# Power_CH340T.net
KiCad netlist of a schematic drawn in Altium Designer
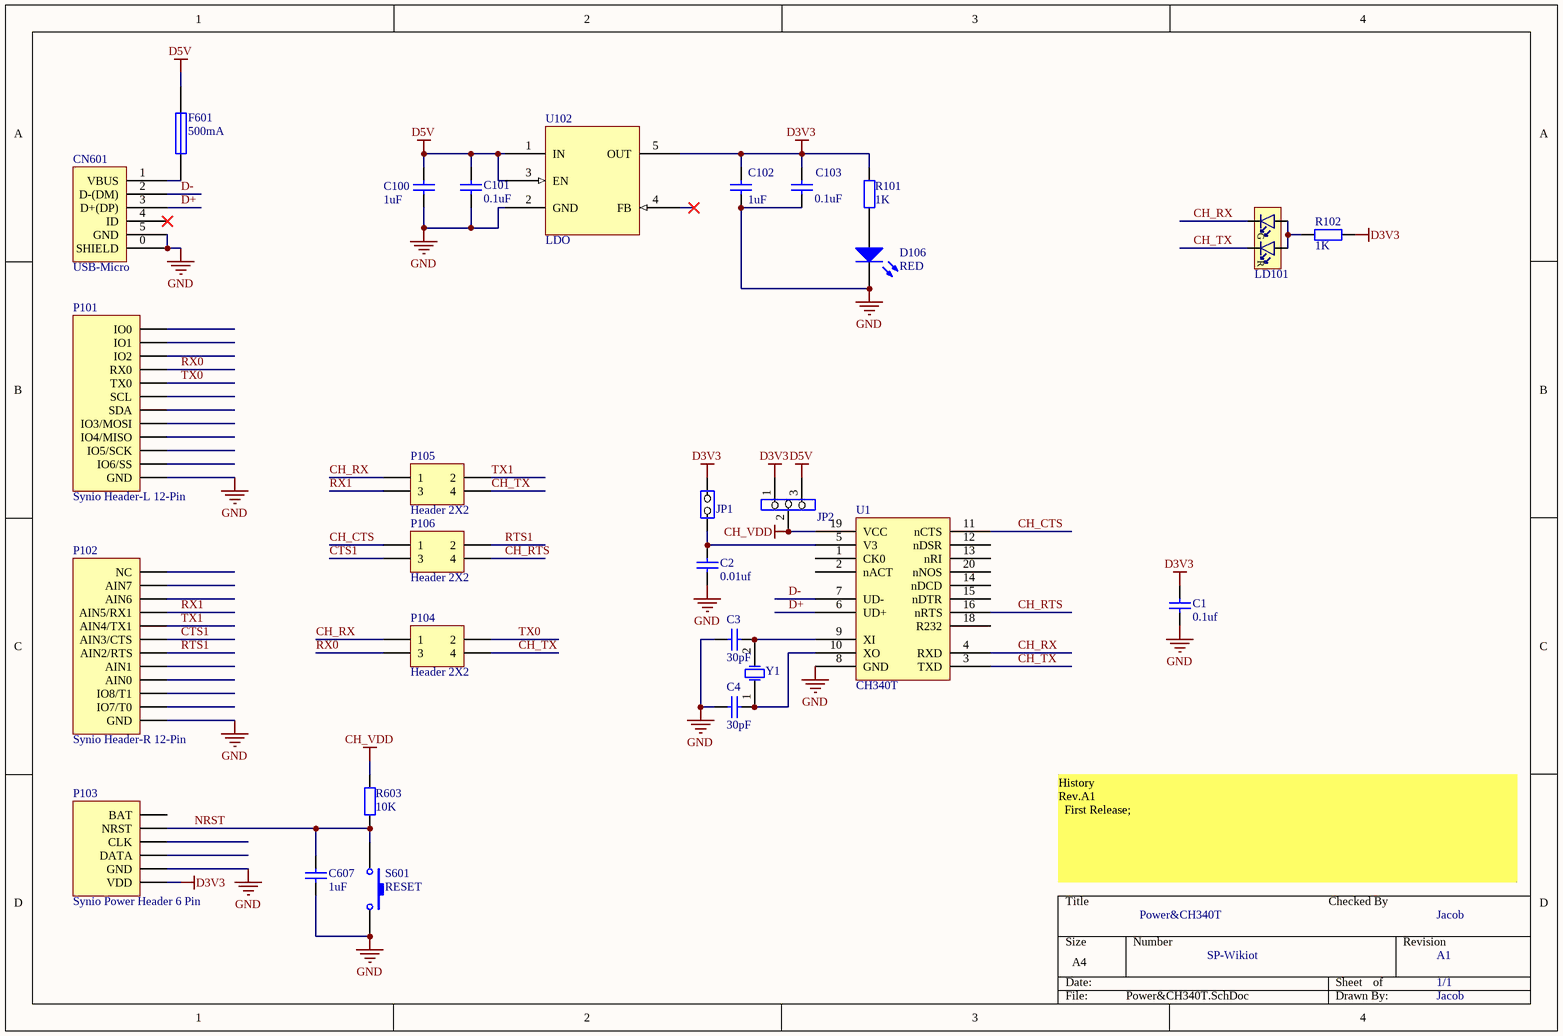
[diagram p0: Power&CH340T.SchDoc]

(export (version "E")
  (design (tool "Eeschema 10.0.6"))
  (components
    (comp (ref "C1")
      (value "0.1uf")
      (footprint "C0603L")
      (description "Capacitor")
      (fields (field (name "Comment") "Cap") (field (name "PUBLISHER") "Altium Limited"))
      (libsource (lib "myintlib") (part "Cap"))
    )
    (comp (ref "C2")
      (value "0.01uf")
      (footprint "C0603L")
      (description "Capacitor")
      (fields (field (name "Comment") "Cap") (field (name "PUBLISHER") "Altium Limited"))
      (libsource (lib "myintlib") (part "Cap"))
    )
    (comp (ref "C3")
      (value "30pF")
      (footprint "C0603L")
      (description "Capacitor")
      (fields (field (name "Comment") "Cap") (field (name "PUBLISHER") "Altium Limited"))
      (libsource (lib "Miscellaneous Devices") (part "Cap"))
    )
    (comp (ref "C4")
      (value "30pF")
      (footprint "C0603L")
      (description "Capacitor")
      (fields (field (name "Comment") "Cap") (field (name "PUBLISHER") "Altium Limited"))
      (libsource (lib "Miscellaneous Devices") (part "Cap"))
    )
    (comp (ref "C100")
      (value "1uF")
      (footprint "0603M")
      (description "Capacitor")
      (libsource (lib "Studio") (part "Cap"))
    )
    (comp (ref "C101")
      (value "0.1uF")
      (footprint "0603M")
      (description "Capacitor")
      (libsource (lib "Studio") (part "Cap"))
    )
    (comp (ref "C102")
      (value "1uF")
      (footprint "0603M")
      (description "Capacitor")
      (libsource (lib "Studio") (part "Cap"))
    )
    (comp (ref "C103")
      (value "0.1uF")
      (footprint "0603M")
      (description "Capacitor")
      (libsource (lib "Studio") (part "Cap"))
    )
    (comp (ref "C607")
      (value "1uF")
      (footprint "C0603L")
      (description "Capacitor")
      (fields (field (name "PUBLISHER") "Altium Limited"))
      (libsource (lib "Miscellaneous Devices") (part "Cap"))
    )
    (comp (ref "CN601")
      (value "USB-Micro")
      (footprint "USB-MICRO-Female-Lite")
      (libsource (lib "Connector") (part "USB-Micro"))
    )
    (comp (ref "D106")
      (value "RED")
      (footprint "0603pn")
      (description "Typical INFRARED GaAs LED")
      (fields (field (name "PUBLISHER") "Altium Limited"))
      (libsource (lib "Miscellaneous Devices") (part "LED0"))
    )
    (comp (ref "F601")
      (value "500mA")
      (footprint "0805")
      (description "Fuse")
      (fields (field (name "PUBLISHER") "Altium Limited"))
      (libsource (lib "Studio") (part "Fuse 1"))
    )
    (comp (ref "JP1")
      (value "Jumper2-2")
      (footprint "SIP2")
      (description "Jumper2")
      (libsource (lib "Misc") (part "Jumper2-2"))
    )
    (comp (ref "JP2") (value "Jumper3") (footprint "SIP3") (libsource (lib "Misc") (part "Jumper3")))
    (comp (ref "LD101")
      (value "LTST-C195KGJRKT")
      (footprint "0805-LED-Bi")
      (description "Avago, HSMF-A203 Bi-Color LED")
      (fields
        (field (name "MANUFACTURER") "Lite-On Inc")
        (field (name "2ND SOURCE PART NUMBER") "859-LTST-C195KGJRKT")
        (field (name "PUBLISHER") "Nordic Semiconductor")
      )
      (libsource (lib "Misc") (part "LED-DUAL"))
    )
    (comp (ref "P101")
      (value "Synio Header-L 12-Pin")
      (footprint "HDR1X12")
      (description "Synio Header-L, 12-Pin")
      (fields (field (name "PUBLISHER") "Altium Limited"))
      (libsource (lib "Connector") (part "Synio Header-L 12-Pin"))
    )
    (comp (ref "P102")
      (value "Synio Header-R 12-Pin")
      (footprint "HDR1X12")
      (description "Synio Header-R, 12-Pin")
      (fields (field (name "PUBLISHER") "Altium Limited"))
      (libsource (lib "Connector") (part "Synio Header-R 12-Pin"))
    )
    (comp (ref "P103")
      (value "Synio Power Header 6 Pin")
      (footprint "HDR1X6/2.54MM")
      (libsource (lib "Connector") (part "Synio Power Header 6 Pin"))
    )
    (comp (ref "P104")
      (value "Header 2X2")
      (footprint "HDR2X2/2.54MM")
      (description "Header, 2-Pin, Dual row")
      (fields (field (name "PUBLISHER") "Altium Limited"))
      (libsource (lib "Miscellaneous Connectors") (part "Header 2X2"))
    )
    (comp (ref "P105")
      (value "Header 2X2")
      (footprint "HDR2X2/2.54MM")
      (description "Header, 2-Pin, Dual row")
      (fields (field (name "PUBLISHER") "Altium Limited"))
      (libsource (lib "Miscellaneous Connectors") (part "Header 2X2"))
    )
    (comp (ref "P106")
      (value "Header 2X2")
      (footprint "HDR2X2/2.54MM")
      (description "Header, 2-Pin, Dual row")
      (fields (field (name "PUBLISHER") "Altium Limited"))
      (libsource (lib "Miscellaneous Connectors") (part "Header 2X2"))
    )
    (comp (ref "R101")
      (value "1K")
      (footprint "0603M")
      (description "Resistor")
      (fields (field (name "PUBLISHER") "Altium Limited"))
      (libsource (lib "Miscellaneous Devices") (part "Res2"))
    )
    (comp (ref "R102")
      (value "1K")
      (footprint "0603M")
      (description "Resistor")
      (fields (field (name "PUBLISHER") "Altium Limited"))
      (libsource (lib "") (part "Res2_2"))
    )
    (comp (ref "R603")
      (value "10K")
      (footprint "0603M")
      (description "Resistor")
      (fields (field (name "PUBLISHER") "Altium Limited"))
      (libsource (lib "") (part "Res2_1"))
    )
    (comp (ref "S601")
      (value "RESET")
      (footprint "KEY-2x4-SMD")
      (description "Switch")
      (fields (field (name "PUBLISHER") "Altium Limited"))
      (libsource (lib "Miscellaneous Devices") (part "SW-PB"))
    )
    (comp (ref "U1") (value "CH340T") (footprint "SSOP20") (libsource (lib "Logic") (part "CH340T")))
    (comp (ref "U102")
      (value "LDO")
      (footprint "SOT23-5")
      (description "General LDO SOT23-5")
      (libsource (lib "Power") (part "LDO-SOT23-5"))
    )
    (comp (ref "Y1")
      (value "XTAL")
      (footprint "XTAL_49S")
      (description "Crystal Oscillator")
      (fields (field (name "PUBLISHER") "Altium Limited"))
      (libsource (lib "Miscellaneous Devices") (part "XTAL"))
    )
  )
  (nets
    (net (code "1") (name "/CH_CTS") (class "Default")
      (node (ref "P106") (pin "1") (pinfunction "1_1") (pintype "passive"))
      (node (ref "U1") (pin "11") (pinfunction "nCTS_11") (pintype "power_in"))
    )
    (net (code "2") (name "/CH_RTS") (class "Default")
      (node (ref "P106") (pin "4") (pinfunction "4_4") (pintype "passive"))
      (node (ref "U1") (pin "16") (pinfunction "nRTS_16") (pintype "power_in"))
    )
    (net (code "3") (name "/CH_RX") (class "Default")
      (node (ref "LD101") (pin "1") (pinfunction "C1_1") (pintype "passive"))
      (node (ref "P104") (pin "1") (pinfunction "1_1") (pintype "passive"))
      (node (ref "P105") (pin "1") (pinfunction "1_1") (pintype "passive"))
      (node (ref "U1") (pin "4") (pinfunction "RXD_4") (pintype "passive"))
    )
    (net (code "4") (name "/CH_TX") (class "Default")
      (node (ref "LD101") (pin "2") (pinfunction "C2_2") (pintype "passive"))
      (node (ref "P104") (pin "4") (pinfunction "4_4") (pintype "passive"))
      (node (ref "P105") (pin "4") (pinfunction "4_4") (pintype "passive"))
      (node (ref "U1") (pin "3") (pinfunction "TXD_3") (pintype "passive"))
    )
    (net (code "5") (name "/CTS1") (class "Default")
      (node (ref "P102") (pin "7") (pinfunction "AIN3/CTS_7") (pintype "passive"))
      (node (ref "P106") (pin "3") (pinfunction "3_3") (pintype "passive"))
    )
    (net (code "6") (name "/D+") (class "Default")
      (node (ref "CN601") (pin "3") (pinfunction "D+(DP)_3") (pintype "passive"))
      (node (ref "U1") (pin "6") (pinfunction "UD+_6") (pintype "passive"))
    )
    (net (code "7") (name "/D-") (class "Default")
      (node (ref "CN601") (pin "2") (pinfunction "D-(DM)_2") (pintype "passive"))
      (node (ref "U1") (pin "7") (pinfunction "UD-_7") (pintype "passive"))
    )
    (net (code "8") (name "/NRST") (class "Default")
      (node (ref "C607") (pin "2") (pinfunction "2_2") (pintype "passive"))
      (node (ref "P103") (pin "5") (pinfunction "NRST_5") (pintype "passive"))
      (node (ref "R603") (pin "2") (pinfunction "2_2") (pintype "passive"))
      (node (ref "S601") (pin "2") (pinfunction "2_2") (pintype "passive"))
    )
    (net (code "9") (name "/RTS1") (class "Default")
      (node (ref "P102") (pin "6") (pinfunction "AIN2/RTS_6") (pintype "passive"))
      (node (ref "P106") (pin "2") (pinfunction "2_2") (pintype "passive"))
    )
    (net (code "10") (name "/RX0") (class "Default")
      (node (ref "P101") (pin "9") (pinfunction "RX0_9") (pintype "passive"))
      (node (ref "P104") (pin "3") (pinfunction "3_3") (pintype "passive"))
    )
    (net (code "11") (name "/RX1") (class "Default")
      (node (ref "P102") (pin "9") (pinfunction "AIN5/RX1_9") (pintype "passive"))
      (node (ref "P105") (pin "3") (pinfunction "3_3") (pintype "passive"))
    )
    (net (code "12") (name "/TX0") (class "Default")
      (node (ref "P101") (pin "8") (pinfunction "TX0_8") (pintype "passive"))
      (node (ref "P104") (pin "2") (pinfunction "2_2") (pintype "passive"))
    )
    (net (code "13") (name "/TX1") (class "Default")
      (node (ref "P102") (pin "8") (pinfunction "AIN4/TX1_8") (pintype "passive"))
      (node (ref "P105") (pin "2") (pinfunction "2_2") (pintype "passive"))
    )
    (net (code "14") (name "CH_VDD") (class "Default")
      (node (ref "JP2") (pin "2") (pintype "passive"))
      (node (ref "R603") (pin "1") (pinfunction "1_1") (pintype "passive"))
      (node (ref "U1") (pin "19") (pinfunction "VCC_19") (pintype "passive"))
    )
    (net (code "15") (name "D3V3") (class "Default")
      (node (ref "C1") (pin "2") (pinfunction "2_2") (pintype "passive"))
      (node (ref "C102") (pin "2") (pinfunction "2_2") (pintype "passive"))
      (node (ref "C103") (pin "2") (pinfunction "2_2") (pintype "passive"))
      (node (ref "JP1") (pin "2") (pinfunction "NO_2") (pintype "passive"))
      (node (ref "JP2") (pin "1") (pintype "passive"))
      (node (ref "P103") (pin "1") (pinfunction "VDD_1") (pintype "passive"))
      (node (ref "R101") (pin "2") (pinfunction "2_2") (pintype "passive"))
      (node (ref "R102") (pin "1") (pinfunction "1_1") (pintype "passive"))
      (node (ref "U102") (pin "5") (pinfunction "OUT_5") (pintype "power_in"))
    )
    (net (code "16") (name "D5V") (class "Default")
      (node (ref "C100") (pin "2") (pinfunction "2_2") (pintype "passive"))
      (node (ref "C101") (pin "2") (pinfunction "2_2") (pintype "passive"))
      (node (ref "F601") (pin "1") (pinfunction "1_1") (pintype "passive"))
      (node (ref "JP2") (pin "3") (pintype "passive"))
      (node (ref "U102") (pin "1") (pinfunction "IN_1") (pintype "power_in"))
      (node (ref "U102") (pin "3") (pinfunction "EN_3") (pintype "input"))
    )
    (net (code "17") (name "GND") (class "Default")
      (node (ref "C1") (pin "1") (pinfunction "1_1") (pintype "passive"))
      (node (ref "C100") (pin "1") (pinfunction "1_1") (pintype "passive"))
      (node (ref "C101") (pin "1") (pinfunction "1_1") (pintype "passive"))
      (node (ref "C102") (pin "1") (pinfunction "1_1") (pintype "passive"))
      (node (ref "C103") (pin "1") (pinfunction "1_1") (pintype "passive"))
      (node (ref "C2") (pin "2") (pinfunction "2_2") (pintype "passive"))
      (node (ref "C3") (pin "2") (pinfunction "2_2") (pintype "passive"))
      (node (ref "C4") (pin "2") (pinfunction "2_2") (pintype "passive"))
      (node (ref "C607") (pin "1") (pinfunction "1_1") (pintype "passive"))
      (node (ref "CN601") (pin "0") (pinfunction "SHIELD_0") (pintype "passive"))
      (node (ref "CN601") (pin "5") (pinfunction "GND_5") (pintype "passive"))
      (node (ref "D106") (pin "2") (pinfunction "K_2") (pintype "passive"))
      (node (ref "P101") (pin "1") (pinfunction "GND_1") (pintype "passive"))
      (node (ref "P102") (pin "1") (pinfunction "GND_1") (pintype "passive"))
      (node (ref "P103") (pin "2") (pinfunction "GND_2") (pintype "passive"))
      (node (ref "S601") (pin "1") (pinfunction "1_1") (pintype "passive"))
      (node (ref "U1") (pin "8") (pinfunction "GND_8") (pintype "passive"))
      (node (ref "U102") (pin "2") (pinfunction "GND_2") (pintype "power_in"))
    )
    (net (code "18") (name "Net-(CN601-VBUS)") (class "Default")
      (node (ref "CN601") (pin "1") (pinfunction "VBUS_1") (pintype "passive"))
      (node (ref "F601") (pin "2") (pinfunction "2_2") (pintype "passive"))
    )
    (net (code "19") (name "Net-(D106-A)") (class "Default")
      (node (ref "D106") (pin "1") (pinfunction "A_1") (pintype "passive"))
      (node (ref "R101") (pin "1") (pinfunction "1_1") (pintype "passive"))
    )
    (net (code "20") (name "Net-(JP1-COMMON)") (class "Default")
      (node (ref "C2") (pin "1") (pinfunction "1_1") (pintype "passive"))
      (node (ref "JP1") (pin "1") (pinfunction "COMMON_1") (pintype "passive"))
      (node (ref "U1") (pin "5") (pinfunction "V3_5") (pintype "passive"))
    )
    (net (code "21") (name "Net-(LD101-A1)") (class "Default")
      (node (ref "LD101") (pin "3") (pinfunction "A2_3") (pintype "passive"))
      (node (ref "LD101") (pin "4") (pinfunction "A1_4") (pintype "passive"))
      (node (ref "R102") (pin "2") (pinfunction "2_2") (pintype "passive"))
    )
    (net (code "22") (name "Net-(U1-XI)") (class "Default")
      (node (ref "C3") (pin "1") (pinfunction "1_1") (pintype "passive"))
      (node (ref "U1") (pin "9") (pinfunction "XI_9") (pintype "passive"))
      (node (ref "Y1") (pin "2") (pinfunction "OSC2_2") (pintype "passive"))
    )
    (net (code "23") (name "Net-(U1-XO)") (class "Default")
      (node (ref "C4") (pin "1") (pinfunction "1_1") (pintype "passive"))
      (node (ref "U1") (pin "10") (pinfunction "XO_10") (pintype "passive"))
      (node (ref "Y1") (pin "1") (pinfunction "OSC1_1") (pintype "passive"))
    )
    (net (code "24") (name "unconnected-(CN601-ID-Pad4)") (class "Default")
      (node (ref "CN601") (pin "4") (pinfunction "ID_4") (pintype "passive+no_connect"))
    )
    (net (code "25") (name "unconnected-(P101-IO0-Pad12)") (class "Default")
      (node (ref "P101") (pin "12") (pinfunction "IO0_12") (pintype "passive"))
    )
    (net (code "26") (name "unconnected-(P101-IO1-Pad11)") (class "Default")
      (node (ref "P101") (pin "11") (pinfunction "IO1_11") (pintype "passive"))
    )
    (net (code "27") (name "unconnected-(P101-IO2-Pad10)") (class "Default")
      (node (ref "P101") (pin "10") (pinfunction "IO2_10") (pintype "passive"))
    )
    (net (code "28") (name "unconnected-(P101-IO3{slash}MOSI-Pad5)") (class "Default")
      (node (ref "P101") (pin "5") (pinfunction "IO3/MOSI_5") (pintype "passive"))
    )
    (net (code "29") (name "unconnected-(P101-IO4{slash}MISO-Pad4)") (class "Default")
      (node (ref "P101") (pin "4") (pinfunction "IO4/MISO_4") (pintype "passive"))
    )
    (net (code "30") (name "unconnected-(P101-IO5{slash}SCK-Pad3)") (class "Default")
      (node (ref "P101") (pin "3") (pinfunction "IO5/SCK_3") (pintype "passive"))
    )
    (net (code "31") (name "unconnected-(P101-IO6{slash}SS-Pad2)") (class "Default")
      (node (ref "P101") (pin "2") (pinfunction "IO6/SS_2") (pintype "passive"))
    )
    (net (code "32") (name "unconnected-(P101-SCL-Pad7)") (class "Default")
      (node (ref "P101") (pin "7") (pinfunction "SCL_7") (pintype "passive"))
    )
    (net (code "33") (name "unconnected-(P101-SDA-Pad6)") (class "Default")
      (node (ref "P101") (pin "6") (pinfunction "SDA_6") (pintype "passive"))
    )
    (net (code "34") (name "unconnected-(P102-AIN0-Pad4)") (class "Default")
      (node (ref "P102") (pin "4") (pinfunction "AIN0_4") (pintype "passive"))
    )
    (net (code "35") (name "unconnected-(P102-AIN1-Pad5)") (class "Default")
      (node (ref "P102") (pin "5") (pinfunction "AIN1_5") (pintype "passive"))
    )
    (net (code "36") (name "unconnected-(P102-AIN6-Pad10)") (class "Default")
      (node (ref "P102") (pin "10") (pinfunction "AIN6_10") (pintype "passive"))
    )
    (net (code "37") (name "unconnected-(P102-AIN7-Pad11)") (class "Default")
      (node (ref "P102") (pin "11") (pinfunction "AIN7_11") (pintype "passive"))
    )
    (net (code "38") (name "unconnected-(P102-IO7{slash}T0-Pad2)") (class "Default")
      (node (ref "P102") (pin "2") (pinfunction "IO7/T0_2") (pintype "passive"))
    )
    (net (code "39") (name "unconnected-(P102-IO8{slash}T1-Pad3)") (class "Default")
      (node (ref "P102") (pin "3") (pinfunction "IO8/T1_3") (pintype "passive"))
    )
    (net (code "40") (name "unconnected-(P102-NC-Pad12)") (class "Default")
      (node (ref "P102") (pin "12") (pinfunction "NC_12") (pintype "passive"))
    )
    (net (code "41") (name "unconnected-(P103-BAT-Pad6)") (class "Default")
      (node (ref "P103") (pin "6") (pinfunction "BAT_6") (pintype "passive"))
    )
    (net (code "42") (name "unconnected-(P103-CLK-Pad4)") (class "Default")
      (node (ref "P103") (pin "4") (pinfunction "CLK_4") (pintype "passive"))
    )
    (net (code "43") (name "unconnected-(P103-DATA-Pad3)") (class "Default")
      (node (ref "P103") (pin "3") (pinfunction "DATA_3") (pintype "passive"))
    )
    (net (code "44") (name "unconnected-(U1-CK0-Pad1)") (class "Default")
      (node (ref "U1") (pin "1") (pinfunction "CK0_1") (pintype "power_in"))
    )
    (net (code "45") (name "unconnected-(U1-R232-Pad18)") (class "Default")
      (node (ref "U1") (pin "18") (pinfunction "R232_18") (pintype "power_in"))
    )
    (net (code "46") (name "unconnected-(U1-nACT-Pad2)") (class "Default")
      (node (ref "U1") (pin "2") (pinfunction "nACT_2") (pintype "power_in"))
    )
    (net (code "47") (name "unconnected-(U1-nDCD-Pad14)") (class "Default")
      (node (ref "U1") (pin "14") (pinfunction "nDCD_14") (pintype "power_in"))
    )
    (net (code "48") (name "unconnected-(U1-nDSR-Pad12)") (class "Default")
      (node (ref "U1") (pin "12") (pinfunction "nDSR_12") (pintype "power_in"))
    )
    (net (code "49") (name "unconnected-(U1-nDTR-Pad15)") (class "Default")
      (node (ref "U1") (pin "15") (pinfunction "nDTR_15") (pintype "power_in"))
    )
    (net (code "50") (name "unconnected-(U1-nNOS-Pad20)") (class "Default")
      (node (ref "U1") (pin "20") (pinfunction "nNOS_20") (pintype "passive"))
    )
    (net (code "51") (name "unconnected-(U1-nRI-Pad13)") (class "Default")
      (node (ref "U1") (pin "13") (pinfunction "nRI_13") (pintype "power_in"))
    )
    (net (code "52") (name "unconnected-(U102-FB-Pad4)") (class "Default")
      (node (ref "U102") (pin "4") (pinfunction "FB_4") (pintype "input+no_connect"))
    )
  )
)
